# inner-led.net
KiCad netlist of a schematic drawn in EAGLE
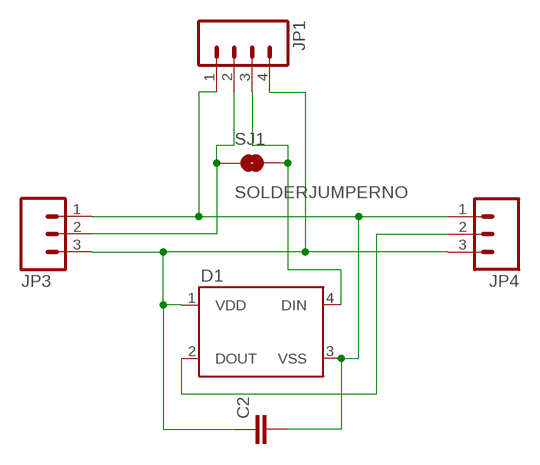
[diagram p0: schematic, sheet 1]

(export (version "E")
  (design (tool "Eeschema 10.0.6"))
  (components
    (comp (ref "C2")
      (value "CAP0805")
      (footprint "eagle-import:0805")
      (libsource (lib "eagle-import") (part "CAP0805"))
    )
    (comp (ref "D1")
      (value "WS2812B")
      (footprint "eagle-import:WS2812B")
      (libsource (lib "eagle-import") (part "WS2812B"))
    )
    (comp (ref "JP1")
      (value "M04NO_SILK_ALL_ROUND")
      (footprint "eagle-import:1X04_NO_SILK_ALL_ROUND")
      (libsource (lib "eagle-import") (part "M04NO_SILK_ALL_ROUND"))
    )
    (comp (ref "JP3")
      (value "M031X03_NO_SILK")
      (footprint "eagle-import:1X03_NO_SILK")
      (libsource (lib "eagle-import") (part "M031X03_NO_SILK"))
    )
    (comp (ref "JP4")
      (value "M031X03_NO_SILK")
      (footprint "eagle-import:1X03_NO_SILK")
      (libsource (lib "eagle-import") (part "M031X03_NO_SILK"))
    )
    (comp (ref "SJ1")
      (value "SOLDERJUMPERNO")
      (footprint "eagle-import:SJ_2S-NO")
      (libsource (lib "eagle-import") (part "SOLDERJUMPERNO"))
    )
  )
  (nets
    (net (code "1") (name "Net-(D1-DIN)") (class "Default")
      (node (ref "D1") (pin "4") (pinfunction "DIN_4") (pintype "input"))
      (node (ref "JP1") (pin "3") (pinfunction "3_3") (pintype "passive"))
      (node (ref "SJ1") (pin "2") (pinfunction "2_2") (pintype "passive"))
    )
    (net (code "2") (name "Net-(D1-DOUT)") (class "Default")
      (node (ref "D1") (pin "2") (pinfunction "DOUT_2") (pintype "output"))
      (node (ref "JP4") (pin "2") (pinfunction "2_2") (pintype "passive"))
    )
    (net (code "3") (name "Net-(D1-VDD)") (class "Default")
      (node (ref "C2") (pin "1") (pinfunction "1_1") (pintype "passive"))
      (node (ref "D1") (pin "1") (pinfunction "VDD_1") (pintype "power_in"))
      (node (ref "JP1") (pin "4") (pinfunction "4_4") (pintype "passive"))
      (node (ref "JP3") (pin "3") (pinfunction "3_3") (pintype "passive"))
      (node (ref "JP4") (pin "3") (pinfunction "3_3") (pintype "passive"))
    )
    (net (code "4") (name "Net-(D1-VSS)") (class "Default")
      (node (ref "C2") (pin "2") (pinfunction "2_2") (pintype "passive"))
      (node (ref "D1") (pin "3") (pinfunction "VSS_3") (pintype "power_in"))
      (node (ref "JP1") (pin "1") (pinfunction "1_1") (pintype "passive"))
      (node (ref "JP3") (pin "1") (pinfunction "1_1") (pintype "passive"))
      (node (ref "JP4") (pin "1") (pinfunction "1_1") (pintype "passive"))
    )
    (net (code "5") (name "Net-(JP1-Pad2)") (class "Default")
      (node (ref "JP1") (pin "2") (pinfunction "2_2") (pintype "passive"))
      (node (ref "JP3") (pin "2") (pinfunction "2_2") (pintype "passive"))
      (node (ref "SJ1") (pin "1") (pinfunction "1_1") (pintype "passive"))
    )
  )
)
